# SCHEMATICS_TAKEMINAKATA.net
KiCad netlist of a schematic drawn in EasyEDA
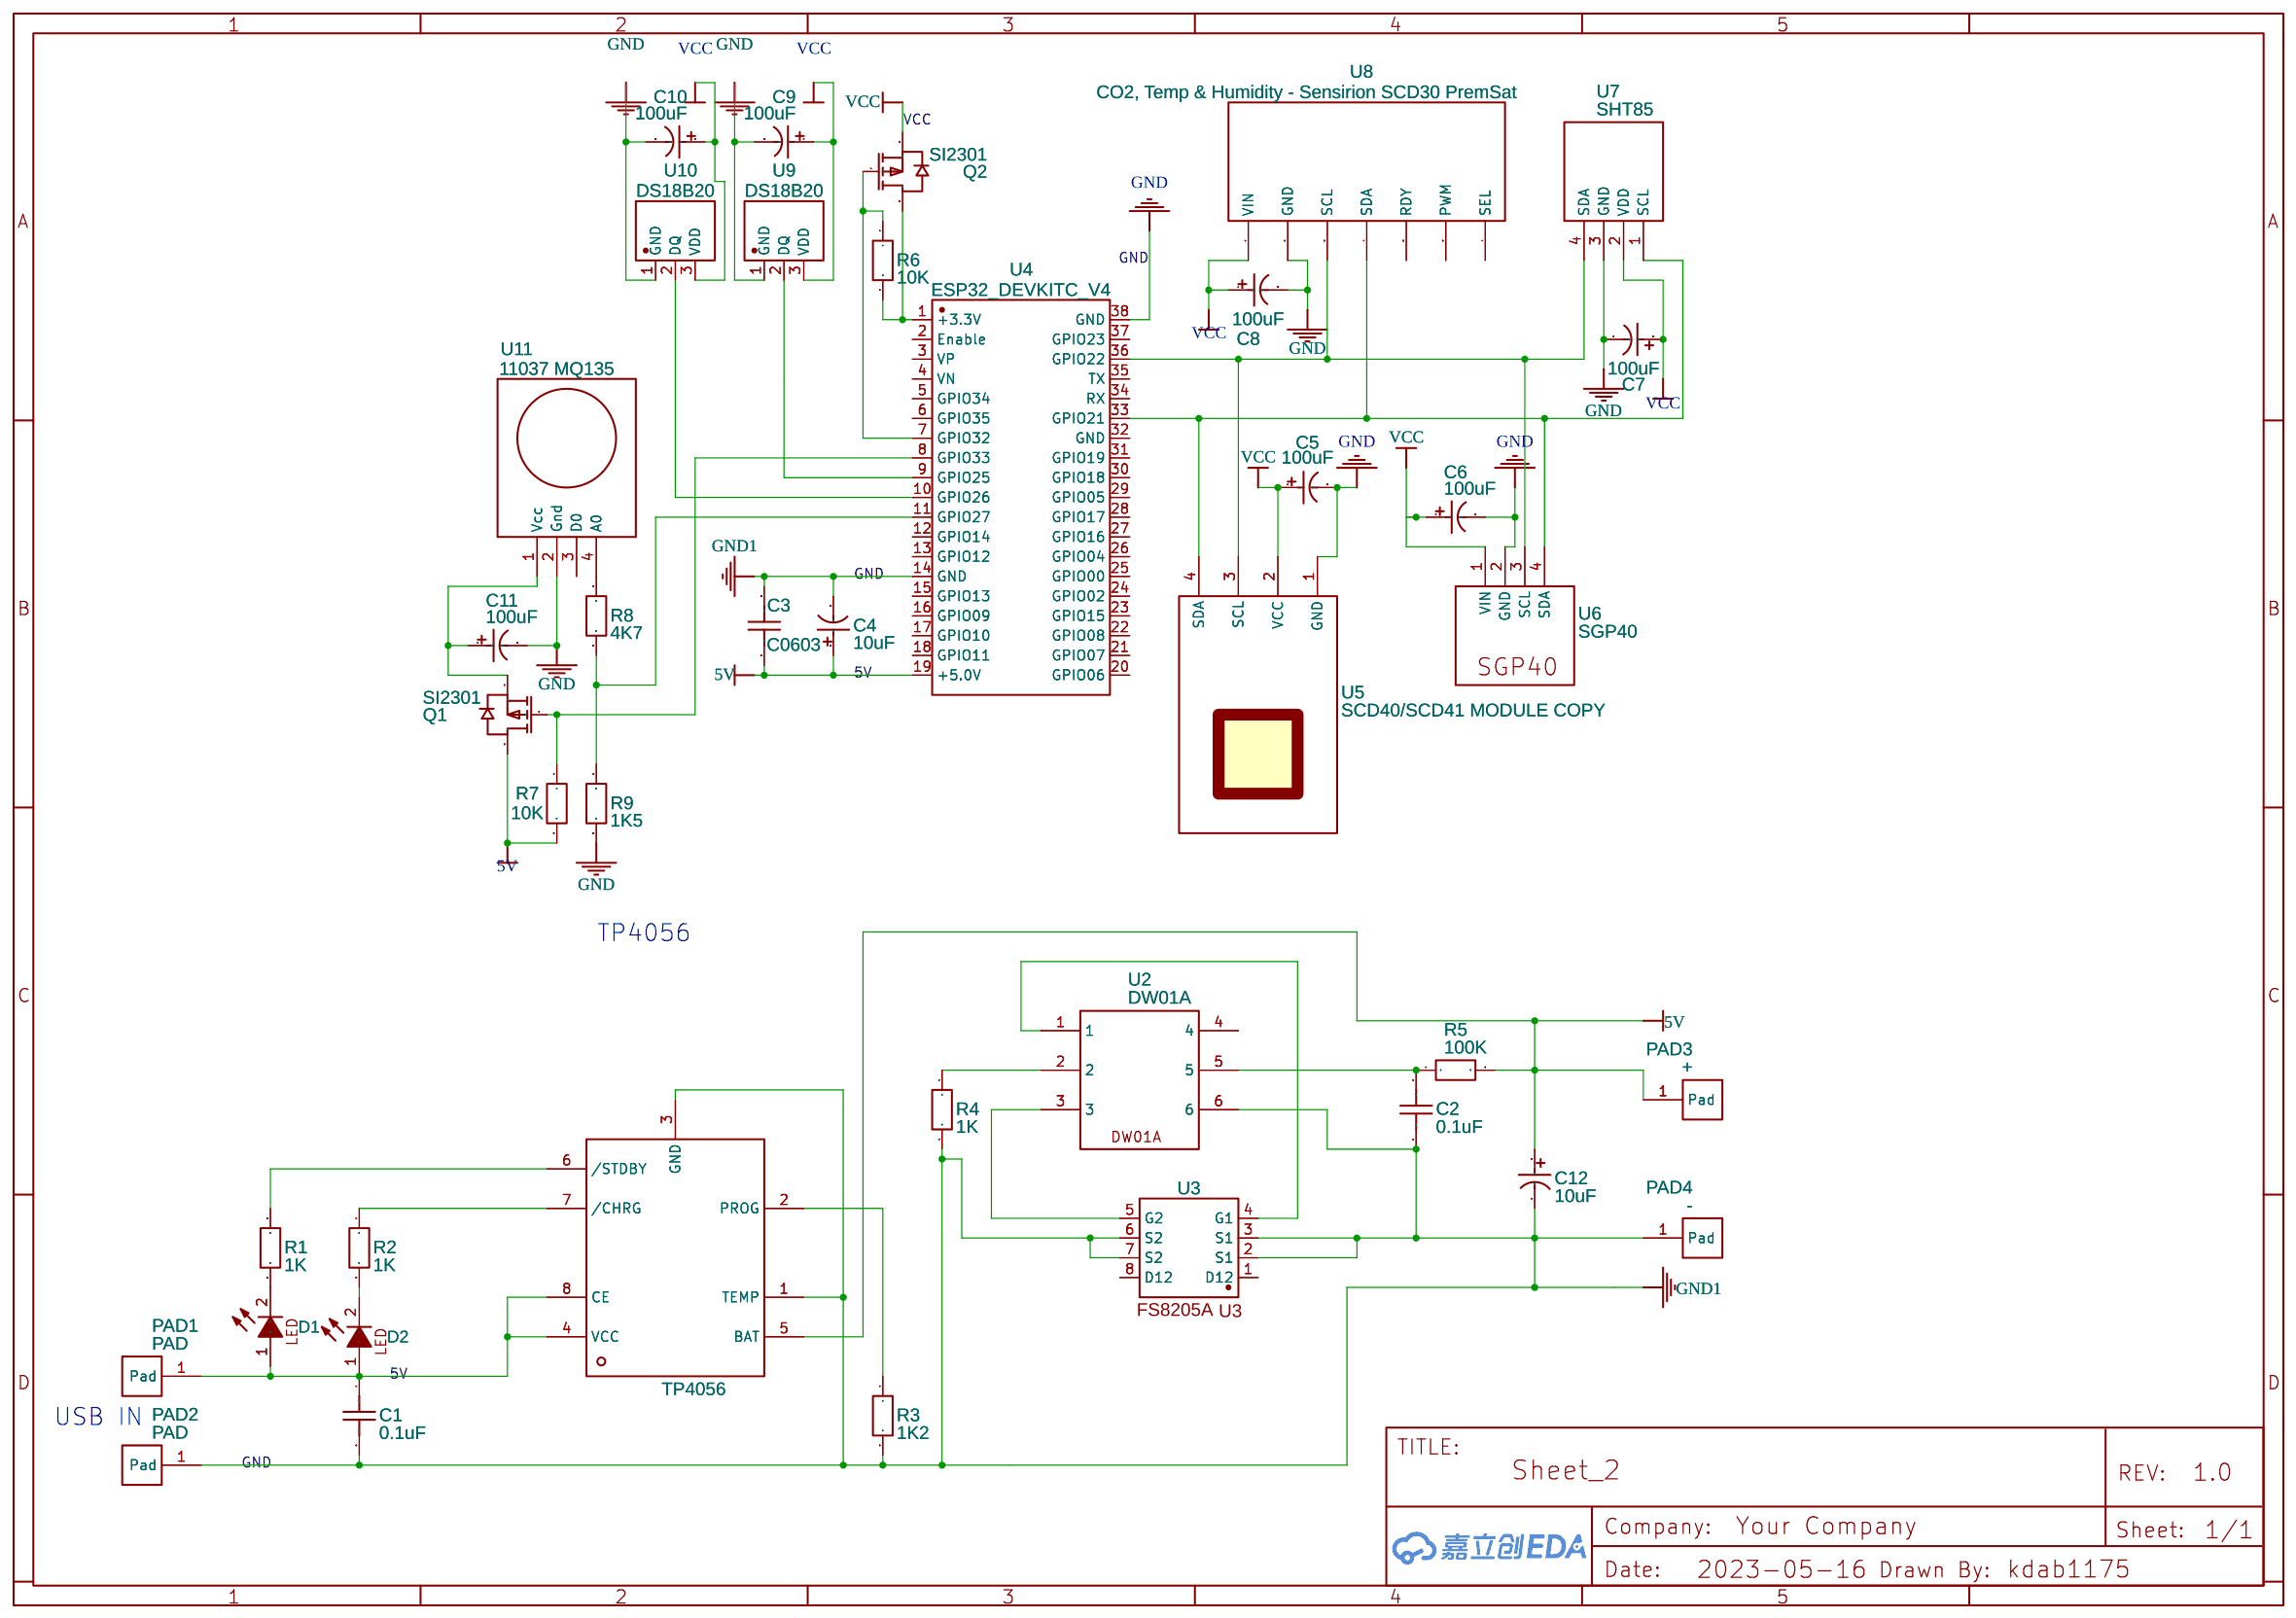
[diagram p0: schematic sheet]

(export (version "E")
  (design (tool "Eeschema 10.0.6"))
  (components
    (comp (ref "C1") (value "0.1uF") (libsource (lib "") (part "C_0603_US")))
    (comp (ref "C2") (value "0.1uF") (libsource (lib "") (part "C_0603_US")))
    (comp (ref "C3")
      (value "C0603")
      (fields (field (name "BOM_Manufacturer Part") "10uF") (field (name "BOM_Supplier Part") "C15415"))
      (libsource (lib "") (part "C 0603"))
    )
    (comp (ref "C4")
      (value "10uF")
      (fields
        (field (name "BOM_Manufacturer Part") "KF106M016B05RR0VH2FP0")
        (field (name "BOM_Supplier Part") "C43798")
      )
      (libsource (lib "") (part "10uF 16V 3*5"))
    )
    (comp (ref "C5")
      (value "100uF")
      (fields
        (field (name "BOM_Manufacturer Part") "100uF 35V 6.3*11")
        (field (name "BOM_Supplier Part") "C45076")
      )
      (libsource (lib "") (part "100uF 35V 6.3*11_C45076_1"))
    )
    (comp (ref "C6")
      (value "100uF")
      (fields
        (field (name "BOM_Manufacturer Part") "100uF 35V 6.3*11")
        (field (name "BOM_Supplier Part") "C45076")
      )
      (libsource (lib "") (part "100uF 35V 6.3*11_C45076_1"))
    )
    (comp (ref "C7")
      (value "100uF")
      (fields
        (field (name "BOM_Manufacturer Part") "100uF 35V 6.3*11")
        (field (name "BOM_Supplier Part") "C45076")
      )
      (libsource (lib "") (part "100uF 35V 6.3*11_C45076_2"))
    )
    (comp (ref "C8")
      (value "100uF")
      (fields
        (field (name "BOM_Manufacturer Part") "100uF 35V 6.3*11")
        (field (name "BOM_Supplier Part") "C45076")
      )
      (libsource (lib "") (part "100uF 35V 6.3*11_C45076_1"))
    )
    (comp (ref "C9")
      (value "100uF")
      (fields
        (field (name "BOM_Manufacturer Part") "100uF 35V 6.3*11")
        (field (name "BOM_Supplier Part") "C45076")
      )
      (libsource (lib "") (part "100uF 35V 6.3*11_C45076"))
    )
    (comp (ref "C10")
      (value "100uF")
      (fields
        (field (name "BOM_Manufacturer Part") "100uF 35V 6.3*11")
        (field (name "BOM_Supplier Part") "C45076")
      )
      (libsource (lib "") (part "100uF 35V 6.3*11_C45076"))
    )
    (comp (ref "C11")
      (value "100uF")
      (fields
        (field (name "BOM_Manufacturer Part") "100uF 35V 6.3*11")
        (field (name "BOM_Supplier Part") "C45076")
      )
      (libsource (lib "") (part "100uF 35V 6.3*11_C45076_1"))
    )
    (comp (ref "C12")
      (value "10uF")
      (fields
        (field (name "BOM_Manufacturer Part") "KF106M016B05RR0VH2FP0")
        (field (name "BOM_Supplier Part") "C43798")
      )
      (libsource (lib "") (part "10uF 16V 3*5_1"))
    )
    (comp (ref "D1")
      (value "LED")
      (fields (field (name "BOM_Manufacturer Part") "5600") (field (name "BOM_Supplier Part") "L20325-ND"))
      (libsource (lib "") (part "LED"))
    )
    (comp (ref "D2")
      (value "LED COPY")
      (fields (field (name "BOM_Manufacturer Part") "5600") (field (name "BOM_Supplier Part") "L20325-ND"))
      (libsource (lib "") (part "LED"))
    )
    (comp (ref "PAD1") (value "PAD") (libsource (lib "") (part "PAD COPY COPY_1")))
    (comp (ref "PAD2") (value "PAD") (libsource (lib "") (part "PAD COPY COPY_1")))
    (comp (ref "PAD3") (value "+") (libsource (lib "") (part "PAD COPY COPY")))
    (comp (ref "PAD4") (value "-") (libsource (lib "") (part "PAD COPY COPY")))
    (comp (ref "Q1")
      (value "SI2301")
      (fields (field (name "BOM_Manufacturer Part") "SI2301DS") (field (name "BOM_Supplier Part") "C2841444"))
      (libsource (lib "") (part "SI2301DS_TH"))
    )
    (comp (ref "Q2")
      (value "SI2301")
      (fields (field (name "BOM_Manufacturer Part") "SI2301DS") (field (name "BOM_Supplier Part") "C2841444"))
      (libsource (lib "") (part "SI2301DS_TH_1"))
    )
    (comp (ref "R1") (value "1K") (libsource (lib "") (part "R_0603_EU")))
    (comp (ref "R2") (value "1K") (libsource (lib "") (part "R_0603_EU")))
    (comp (ref "R3") (value "1K2") (libsource (lib "") (part "R_0603_EU")))
    (comp (ref "R4") (value "1K") (libsource (lib "") (part "R_0603_EU")))
    (comp (ref "R5") (value "100K") (libsource (lib "") (part "R_0603_EU_1")))
    (comp (ref "R6") (value "10K") (libsource (lib "") (part "R_0603_EU")))
    (comp (ref "R7") (value "10K") (libsource (lib "") (part "R_0603_EU")))
    (comp (ref "R8") (value "4K7") (libsource (lib "") (part "R_0603_EU")))
    (comp (ref "R9") (value "1K5") (libsource (lib "") (part "R_0603_EU")))
    (comp (ref "U1")
      (value "TP4056")
      (fields
        (field (name "BOM_Manufacturer Part") "TP4056-42-SOP8-PP")
        (field (name "BOM_Supplier Part") "3656")
      )
      (libsource (lib "") (part "TP4056"))
    )
    (comp (ref "U2") (value "DW01A") (libsource (lib "") (part "DW01A")))
    (comp (ref "U3") (value "FS8205A MODIF") (libsource (lib "") (part "FS8205A MODIF")))
    (comp (ref "U4")
      (value "ESP32_DEVKITC_V4")
      (fields (field (name "BOM_Supplier Part") "A5130"))
      (libsource (lib "") (part "ESP32_DEVKITC_V4"))
    )
    (comp (ref "U5") (value "SCD40/SCD41 MODULE COPY") (libsource (lib "") (part "SCD40/SCD41 MODULE COPY")))
    (comp (ref "U6") (value "SGP40") (libsource (lib "") (part "SGP40")))
    (comp (ref "U7")
      (value "SHT85")
      (fields (field (name "BOM_Supplier Part") "403-SHT85"))
      (libsource (lib "") (part "SHT85"))
    )
    (comp (ref "U8")
      (value "CO2, Temp & Humidity - Sensirion SCD30 PremSat")
      (fields
        (field (name "BOM_Manufacturer Part") "SCD30")
        (field (name "BOM_Supplier Part") "1649-1098-ND")
      )
      (libsource (lib "") (part "CO2, Temp & Humidity - Sensirion SCD30 PremSat"))
    )
    (comp (ref "U9")
      (value "DS18B20")
      (fields (field (name "BOM_Supplier Part") "C5379069"))
      (libsource (lib "") (part "DS18B20_C5379069"))
    )
    (comp (ref "U10")
      (value "DS18B20")
      (fields (field (name "BOM_Supplier Part") "C5379069"))
      (libsource (lib "") (part "DS18B20_C5379069"))
    )
    (comp (ref "U11") (value "11037 MQ135") (libsource (lib "") (part "11037 MQ135")))
  )
  (nets
    (net (code "1") (name "5V") (class "Default")
      (node (ref "C1") (pin "1") (pinfunction "1_1") (pintype "unspecified"))
      (node (ref "C12") (pin "1") (pinfunction "1_1") (pintype "input"))
      (node (ref "C3") (pin "1") (pinfunction "1_1") (pintype "unspecified"))
      (node (ref "C4") (pin "1") (pinfunction "1_1") (pintype "input"))
      (node (ref "D1") (pin "1") (pinfunction "A_1") (pintype "unspecified"))
      (node (ref "D2") (pin "1") (pinfunction "A_1") (pintype "unspecified"))
      (node (ref "PAD1") (pin "1") (pinfunction "Pad_1") (pintype "unspecified"))
      (node (ref "PAD3") (pin "1") (pinfunction "Pad_1") (pintype "unspecified"))
      (node (ref "Q1") (pin "3") (pinfunction "D_3") (pintype "unspecified"))
      (node (ref "R5") (pin "2") (pinfunction "2_2") (pintype "unspecified"))
      (node (ref "R7") (pin "2") (pinfunction "2_2") (pintype "unspecified"))
      (node (ref "U1") (pin "4") (pinfunction "VCC_4") (pintype "unspecified"))
      (node (ref "U1") (pin "5") (pinfunction "BAT_5") (pintype "unspecified"))
      (node (ref "U1") (pin "8") (pinfunction "CE_8") (pintype "unspecified"))
      (node (ref "U4") (pin "19") (pinfunction "+5.0V_19") (pintype "unspecified"))
    )
    (net (code "2") (name "GND") (class "Default")
      (node (ref "C1") (pin "2") (pinfunction "2_2") (pintype "unspecified"))
      (node (ref "C10") (pin "2") (pinfunction "2_2") (pintype "input"))
      (node (ref "C11") (pin "2") (pinfunction "2_2") (pintype "input"))
      (node (ref "C12") (pin "2") (pinfunction "2_2") (pintype "input"))
      (node (ref "C2") (pin "2") (pinfunction "2_2") (pintype "unspecified"))
      (node (ref "C3") (pin "2") (pinfunction "2_2") (pintype "unspecified"))
      (node (ref "C4") (pin "2") (pinfunction "2_2") (pintype "input"))
      (node (ref "C5") (pin "2") (pinfunction "2_2") (pintype "input"))
      (node (ref "C6") (pin "2") (pinfunction "2_2") (pintype "input"))
      (node (ref "C7") (pin "2") (pinfunction "2_2") (pintype "input"))
      (node (ref "C8") (pin "2") (pinfunction "2_2") (pintype "input"))
      (node (ref "C9") (pin "2") (pinfunction "2_2") (pintype "input"))
      (node (ref "PAD2") (pin "1") (pinfunction "Pad_1") (pintype "unspecified"))
      (node (ref "PAD4") (pin "1") (pinfunction "Pad_1") (pintype "unspecified"))
      (node (ref "R3") (pin "2") (pinfunction "2_2") (pintype "unspecified"))
      (node (ref "R4") (pin "2") (pinfunction "2_2") (pintype "unspecified"))
      (node (ref "R9") (pin "2") (pinfunction "2_2") (pintype "unspecified"))
      (node (ref "U1") (pin "1") (pinfunction "TEMP_1") (pintype "unspecified"))
      (node (ref "U1") (pin "3") (pinfunction "GND_3") (pintype "unspecified"))
      (node (ref "U10") (pin "1") (pinfunction "GND_1") (pintype "unspecified"))
      (node (ref "U11") (pin "2") (pinfunction "Gnd_2") (pintype "unspecified"))
      (node (ref "U2") (pin "6") (pinfunction "6_6") (pintype "unspecified"))
      (node (ref "U3") (pin "2") (pinfunction "S1_2") (pintype "unspecified"))
      (node (ref "U3") (pin "3") (pinfunction "S1_3") (pintype "unspecified"))
      (node (ref "U3") (pin "6") (pinfunction "S2_6") (pintype "unspecified"))
      (node (ref "U3") (pin "7") (pinfunction "S2_7") (pintype "unspecified"))
      (node (ref "U4") (pin "14") (pinfunction "GND_14") (pintype "unspecified"))
      (node (ref "U4") (pin "38") (pinfunction "GND_38") (pintype "unspecified"))
      (node (ref "U5") (pin "1") (pinfunction "GND_1") (pintype "unspecified"))
      (node (ref "U6") (pin "2") (pinfunction "GND_2") (pintype "unspecified"))
      (node (ref "U7") (pin "3") (pinfunction "GND_3") (pintype "unspecified"))
      (node (ref "U8") (pin "2") (pinfunction "GND_2") (pintype "unspecified"))
      (node (ref "U9") (pin "1") (pinfunction "GND_1") (pintype "unspecified"))
    )
    (net (code "3") (name "Net-(C2-Pad1)") (class "Default")
      (node (ref "C2") (pin "1") (pinfunction "1_1") (pintype "unspecified"))
      (node (ref "R5") (pin "1") (pinfunction "1_1") (pintype "unspecified"))
      (node (ref "U2") (pin "5") (pinfunction "5_5") (pintype "unspecified"))
    )
    (net (code "4") (name "Net-(D1-K)") (class "Default")
      (node (ref "D1") (pin "2") (pinfunction "K_2") (pintype "unspecified"))
      (node (ref "R1") (pin "2") (pinfunction "2_2") (pintype "unspecified"))
    )
    (net (code "5") (name "Net-(D2-K)") (class "Default")
      (node (ref "D2") (pin "2") (pinfunction "K_2") (pintype "unspecified"))
      (node (ref "R2") (pin "2") (pinfunction "2_2") (pintype "unspecified"))
    )
    (net (code "6") (name "Net-(Q1-G)") (class "Default")
      (node (ref "Q1") (pin "1") (pinfunction "G_1") (pintype "unspecified"))
      (node (ref "R7") (pin "1") (pinfunction "1_1") (pintype "unspecified"))
      (node (ref "U4") (pin "8") (pinfunction "GPIO33_8") (pintype "unspecified"))
    )
    (net (code "7") (name "Net-(Q1-S)") (class "Default")
      (node (ref "C11") (pin "1") (pinfunction "1_1") (pintype "input"))
      (node (ref "Q1") (pin "2") (pinfunction "S_2") (pintype "unspecified"))
      (node (ref "U11") (pin "1") (pinfunction "Vcc_1") (pintype "unspecified"))
    )
    (net (code "8") (name "Net-(Q2-D)") (class "Default")
      (node (ref "Q2") (pin "3") (pinfunction "D_3") (pintype "unspecified"))
      (node (ref "R6") (pin "2") (pinfunction "2_2") (pintype "unspecified"))
      (node (ref "U4") (pin "1") (pinfunction "+3.3V_1") (pintype "unspecified"))
    )
    (net (code "9") (name "Net-(Q2-G)") (class "Default")
      (node (ref "Q2") (pin "1") (pinfunction "G_1") (pintype "unspecified"))
      (node (ref "R6") (pin "1") (pinfunction "1_1") (pintype "unspecified"))
      (node (ref "U4") (pin "7") (pinfunction "GPIO32_7") (pintype "unspecified"))
    )
    (net (code "10") (name "Net-(R4-Pad1)") (class "Default")
      (node (ref "R4") (pin "1") (pinfunction "1_1") (pintype "unspecified"))
      (node (ref "U2") (pin "2") (pinfunction "2_2") (pintype "unspecified"))
    )
    (net (code "11") (name "Net-(U1-PROG)") (class "Default")
      (node (ref "R3") (pin "1") (pinfunction "1_1") (pintype "unspecified"))
      (node (ref "U1") (pin "2") (pinfunction "PROG_2") (pintype "unspecified"))
    )
    (net (code "12") (name "Net-(U1-{slash}CHRG)") (class "Default")
      (node (ref "R2") (pin "1") (pinfunction "1_1") (pintype "unspecified"))
      (node (ref "U1") (pin "7") (pinfunction "/CHRG_7") (pintype "unspecified"))
    )
    (net (code "13") (name "Net-(U1-{slash}STDBY)") (class "Default")
      (node (ref "R1") (pin "1") (pinfunction "1_1") (pintype "unspecified"))
      (node (ref "U1") (pin "6") (pinfunction "/STDBY_6") (pintype "unspecified"))
    )
    (net (code "14") (name "Net-(U3-G1)") (class "Default")
      (node (ref "U2") (pin "1") (pinfunction "1_1") (pintype "unspecified"))
      (node (ref "U3") (pin "4") (pinfunction "G1_4") (pintype "unspecified"))
    )
    (net (code "15") (name "Net-(U3-G2)") (class "Default")
      (node (ref "U2") (pin "3") (pinfunction "3_3") (pintype "unspecified"))
      (node (ref "U3") (pin "5") (pinfunction "G2_5") (pintype "unspecified"))
    )
    (net (code "16") (name "Net-(U4-GPIO21)") (class "Default")
      (node (ref "U4") (pin "33") (pinfunction "GPIO21_33") (pintype "unspecified"))
      (node (ref "U5") (pin "4") (pinfunction "SDA_4") (pintype "unspecified"))
      (node (ref "U6") (pin "4") (pinfunction "SDA_4") (pintype "unspecified"))
      (node (ref "U7") (pin "1") (pinfunction "SCL_1") (pintype "unspecified"))
      (node (ref "U8") (pin "4") (pinfunction "SDA_4") (pintype "unspecified"))
    )
    (net (code "17") (name "Net-(U4-GPIO22)") (class "Default")
      (node (ref "U4") (pin "36") (pinfunction "GPIO22_36") (pintype "unspecified"))
      (node (ref "U5") (pin "3") (pinfunction "SCL_3") (pintype "unspecified"))
      (node (ref "U6") (pin "3") (pinfunction "SCL_3") (pintype "unspecified"))
      (node (ref "U7") (pin "4") (pinfunction "SDA_4") (pintype "unspecified"))
      (node (ref "U8") (pin "3") (pinfunction "SCL_3") (pintype "unspecified"))
    )
    (net (code "18") (name "Net-(U4-GPIO25)") (class "Default")
      (node (ref "U4") (pin "9") (pinfunction "GPIO25_9") (pintype "unspecified"))
      (node (ref "U9") (pin "2") (pinfunction "DQ_2") (pintype "unspecified"))
    )
    (net (code "19") (name "Net-(U4-GPIO27)") (class "Default")
      (node (ref "R8") (pin "2") (pinfunction "2_2") (pintype "unspecified"))
      (node (ref "R9") (pin "1") (pinfunction "1_1") (pintype "unspecified"))
      (node (ref "U4") (pin "11") (pinfunction "GPIO27_11") (pintype "unspecified"))
    )
    (net (code "20") (name "Net-(U10-DQ)") (class "Default")
      (node (ref "U10") (pin "2") (pinfunction "DQ_2") (pintype "unspecified"))
      (node (ref "U4") (pin "10") (pinfunction "GPIO26_10") (pintype "unspecified"))
    )
    (net (code "21") (name "Net-(U11-A0)") (class "Default")
      (node (ref "R8") (pin "1") (pinfunction "1_1") (pintype "unspecified"))
      (node (ref "U11") (pin "4") (pinfunction "A0_4") (pintype "unspecified"))
    )
    (net (code "22") (name "VCC") (class "Default")
      (node (ref "C10") (pin "1") (pinfunction "1_1") (pintype "input"))
      (node (ref "C5") (pin "1") (pinfunction "1_1") (pintype "input"))
      (node (ref "C6") (pin "1") (pinfunction "1_1") (pintype "input"))
      (node (ref "C7") (pin "1") (pinfunction "1_1") (pintype "input"))
      (node (ref "C8") (pin "1") (pinfunction "1_1") (pintype "input"))
      (node (ref "C9") (pin "1") (pinfunction "1_1") (pintype "input"))
      (node (ref "Q2") (pin "2") (pinfunction "S_2") (pintype "unspecified"))
      (node (ref "U10") (pin "3") (pinfunction "VDD_3") (pintype "unspecified"))
      (node (ref "U5") (pin "2") (pinfunction "VCC_2") (pintype "unspecified"))
      (node (ref "U6") (pin "1") (pinfunction "VIN_1") (pintype "unspecified"))
      (node (ref "U7") (pin "2") (pinfunction "VDD_2") (pintype "unspecified"))
      (node (ref "U8") (pin "1") (pinfunction "VIN_1") (pintype "unspecified"))
      (node (ref "U9") (pin "3") (pinfunction "VDD_3") (pintype "unspecified"))
    )
    (net (code "23") (name "unconnected-(U2-Pad4)") (class "Default")
      (node (ref "U2") (pin "4") (pinfunction "4_4") (pintype "unspecified"))
    )
    (net (code "24") (name "unconnected-(U3-D12-Pad1)") (class "Default")
      (node (ref "U3") (pin "1") (pinfunction "D12_1") (pintype "unspecified"))
    )
    (net (code "25") (name "unconnected-(U3-D12-Pad8)") (class "Default")
      (node (ref "U3") (pin "8") (pinfunction "D12_8") (pintype "unspecified"))
    )
    (net (code "26") (name "unconnected-(U4-Enable-Pad2)") (class "Default")
      (node (ref "U4") (pin "2") (pinfunction "Enable_2") (pintype "unspecified"))
    )
    (net (code "27") (name "unconnected-(U4-GND-Pad32)") (class "Default")
      (node (ref "U4") (pin "32") (pinfunction "GND_32") (pintype "unspecified"))
    )
    (net (code "28") (name "unconnected-(U4-GPIO00-Pad25)") (class "Default")
      (node (ref "U4") (pin "25") (pinfunction "GPIO00_25") (pintype "unspecified"))
    )
    (net (code "29") (name "unconnected-(U4-GPIO02-Pad24)") (class "Default")
      (node (ref "U4") (pin "24") (pinfunction "GPIO02_24") (pintype "unspecified"))
    )
    (net (code "30") (name "unconnected-(U4-GPIO04-Pad26)") (class "Default")
      (node (ref "U4") (pin "26") (pinfunction "GPIO04_26") (pintype "unspecified"))
    )
    (net (code "31") (name "unconnected-(U4-GPIO05-Pad29)") (class "Default")
      (node (ref "U4") (pin "29") (pinfunction "GPIO05_29") (pintype "unspecified"))
    )
    (net (code "32") (name "unconnected-(U4-GPIO06-Pad20)") (class "Default")
      (node (ref "U4") (pin "20") (pinfunction "GPIO06_20") (pintype "unspecified"))
    )
    (net (code "33") (name "unconnected-(U4-GPIO07-Pad21)") (class "Default")
      (node (ref "U4") (pin "21") (pinfunction "GPIO07_21") (pintype "unspecified"))
    )
    (net (code "34") (name "unconnected-(U4-GPIO08-Pad22)") (class "Default")
      (node (ref "U4") (pin "22") (pinfunction "GPIO08_22") (pintype "unspecified"))
    )
    (net (code "35") (name "unconnected-(U4-GPIO09-Pad16)") (class "Default")
      (node (ref "U4") (pin "16") (pinfunction "GPIO09_16") (pintype "unspecified"))
    )
    (net (code "36") (name "unconnected-(U4-GPIO10-Pad17)") (class "Default")
      (node (ref "U4") (pin "17") (pinfunction "GPIO10_17") (pintype "unspecified"))
    )
    (net (code "37") (name "unconnected-(U4-GPIO11-Pad18)") (class "Default")
      (node (ref "U4") (pin "18") (pinfunction "GPIO11_18") (pintype "unspecified"))
    )
    (net (code "38") (name "unconnected-(U4-GPIO12-Pad13)") (class "Default")
      (node (ref "U4") (pin "13") (pinfunction "GPIO12_13") (pintype "unspecified"))
    )
    (net (code "39") (name "unconnected-(U4-GPIO13-Pad15)") (class "Default")
      (node (ref "U4") (pin "15") (pinfunction "GPIO13_15") (pintype "unspecified"))
    )
    (net (code "40") (name "unconnected-(U4-GPIO14-Pad12)") (class "Default")
      (node (ref "U4") (pin "12") (pinfunction "GPIO14_12") (pintype "unspecified"))
    )
    (net (code "41") (name "unconnected-(U4-GPIO15-Pad23)") (class "Default")
      (node (ref "U4") (pin "23") (pinfunction "GPIO15_23") (pintype "unspecified"))
    )
    (net (code "42") (name "unconnected-(U4-GPIO16-Pad27)") (class "Default")
      (node (ref "U4") (pin "27") (pinfunction "GPIO16_27") (pintype "unspecified"))
    )
    (net (code "43") (name "unconnected-(U4-GPIO17-Pad28)") (class "Default")
      (node (ref "U4") (pin "28") (pinfunction "GPIO17_28") (pintype "unspecified"))
    )
    (net (code "44") (name "unconnected-(U4-GPIO18-Pad30)") (class "Default")
      (node (ref "U4") (pin "30") (pinfunction "GPIO18_30") (pintype "unspecified"))
    )
    (net (code "45") (name "unconnected-(U4-GPIO19-Pad31)") (class "Default")
      (node (ref "U4") (pin "31") (pinfunction "GPIO19_31") (pintype "unspecified"))
    )
    (net (code "46") (name "unconnected-(U4-GPIO23-Pad37)") (class "Default")
      (node (ref "U4") (pin "37") (pinfunction "GPIO23_37") (pintype "unspecified"))
    )
    (net (code "47") (name "unconnected-(U4-GPIO34-Pad5)") (class "Default")
      (node (ref "U4") (pin "5") (pinfunction "GPIO34_5") (pintype "unspecified"))
    )
    (net (code "48") (name "unconnected-(U4-GPIO35-Pad6)") (class "Default")
      (node (ref "U4") (pin "6") (pinfunction "GPIO35_6") (pintype "unspecified"))
    )
    (net (code "49") (name "unconnected-(U4-RX-Pad34)") (class "Default")
      (node (ref "U4") (pin "34") (pinfunction "RX_34") (pintype "unspecified"))
    )
    (net (code "50") (name "unconnected-(U4-TX-Pad35)") (class "Default")
      (node (ref "U4") (pin "35") (pinfunction "TX_35") (pintype "unspecified"))
    )
    (net (code "51") (name "unconnected-(U4-VN-Pad4)") (class "Default")
      (node (ref "U4") (pin "4") (pinfunction "VN_4") (pintype "unspecified"))
    )
    (net (code "52") (name "unconnected-(U4-VP-Pad3)") (class "Default")
      (node (ref "U4") (pin "3") (pinfunction "VP_3") (pintype "unspecified"))
    )
    (net (code "53") (name "unconnected-(U8-PWM-Pad6)") (class "Default")
      (node (ref "U8") (pin "6") (pinfunction "PWM_6") (pintype "unspecified"))
    )
    (net (code "54") (name "unconnected-(U8-RDY-Pad5)") (class "Default")
      (node (ref "U8") (pin "5") (pinfunction "RDY_5") (pintype "unspecified"))
    )
    (net (code "55") (name "unconnected-(U8-SEL-Pad7)") (class "Default")
      (node (ref "U8") (pin "7") (pinfunction "SEL_7") (pintype "unspecified"))
    )
    (net (code "56") (name "unconnected-(U11-D0-Pad3)") (class "Default")
      (node (ref "U11") (pin "3") (pinfunction "D0_3") (pintype "unspecified"))
    )
  )
)
